# finalpcbv2.net
KiCad netlist of a schematic drawn in EAGLE
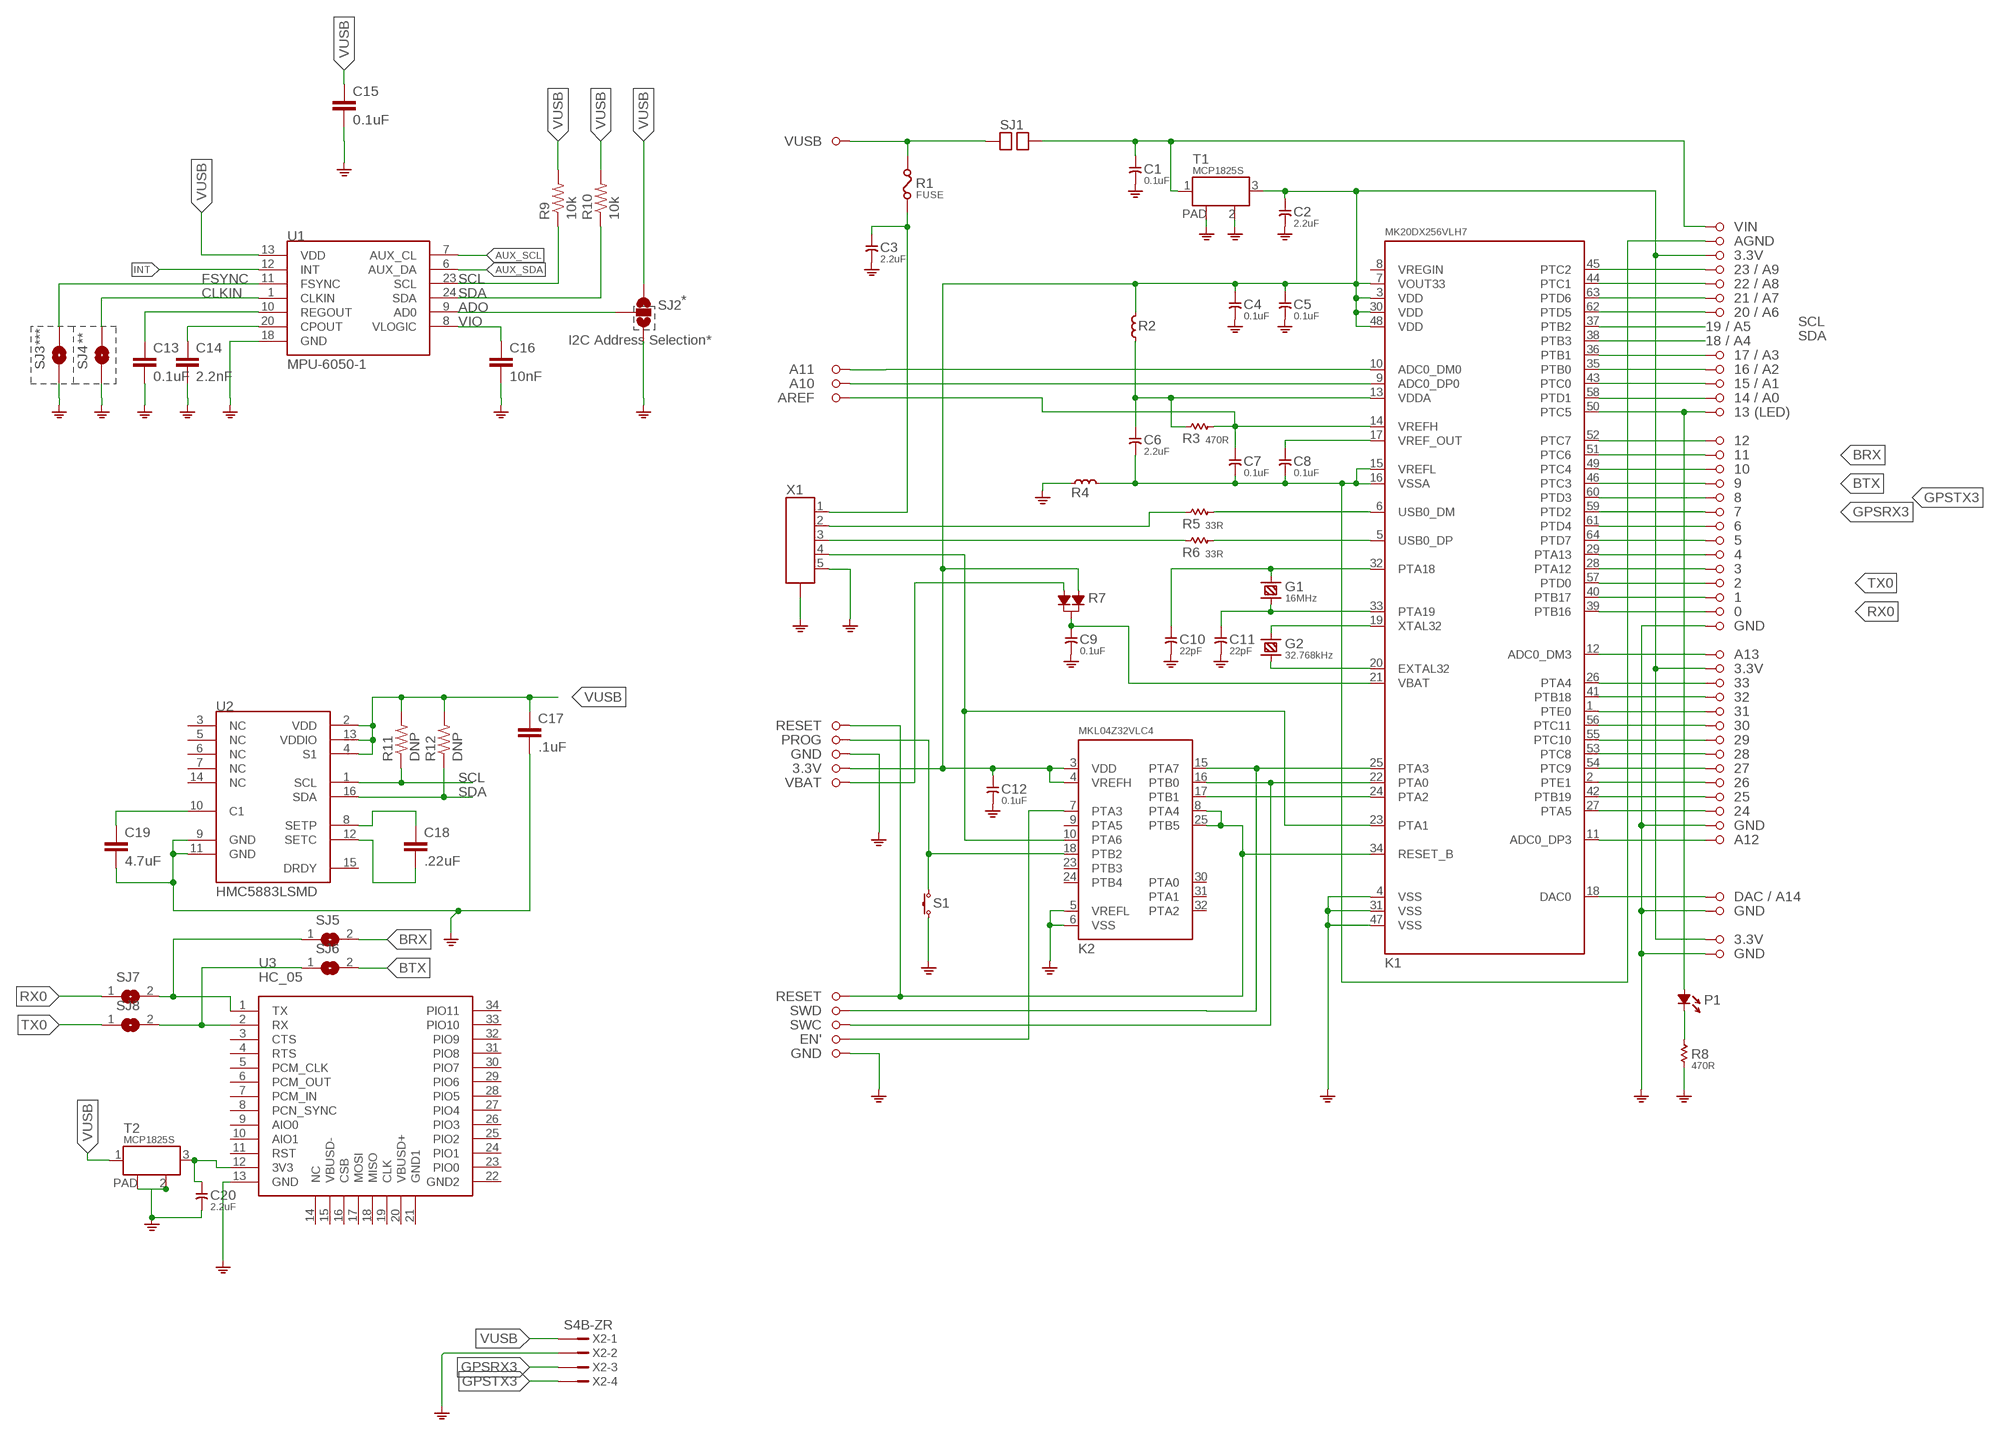
[diagram p0: schematic, sheet 1]

(export (version "E")
  (design (tool "Eeschema 10.0.6"))
  (components
    (comp (ref "C1")
      (value "0.1uF")
      (footprint "eagle-import:C0603")
      (fields (field (name "MF") "Murata Electronics") (field (name "MPN") "GRM188R71C104KA01D"))
      (libsource (lib "eagle-import") (part "CAPACITOR-0.1UF"))
    )
    (comp (ref "C2")
      (value "2.2uF")
      (footprint "eagle-import:C0805")
      (fields (field (name "MF") "Taiyo Yuden") (field (name "MPN") "TMK212B7225KG-TR"))
      (libsource (lib "eagle-import") (part "CAPACITOR-2.2UF"))
    )
    (comp (ref "C3")
      (value "2.2uF")
      (footprint "eagle-import:C0805")
      (fields (field (name "MF") "Taiyo Yuden") (field (name "MPN") "TMK212B7225KG-TR"))
      (libsource (lib "eagle-import") (part "CAPACITOR-2.2UF"))
    )
    (comp (ref "C4")
      (value "0.1uF")
      (footprint "eagle-import:C0603")
      (fields (field (name "MF") "Murata Electronics") (field (name "MPN") "GRM188R71C104KA01D"))
      (libsource (lib "eagle-import") (part "CAPACITOR-0.1UF"))
    )
    (comp (ref "C5")
      (value "0.1uF")
      (footprint "eagle-import:C0603")
      (fields (field (name "MF") "Murata Electronics") (field (name "MPN") "GRM188R71C104KA01D"))
      (libsource (lib "eagle-import") (part "CAPACITOR-0.1UF"))
    )
    (comp (ref "C6")
      (value "2.2uF")
      (footprint "eagle-import:C0805")
      (fields (field (name "MF") "Taiyo Yuden") (field (name "MPN") "TMK212B7225KG-TR"))
      (libsource (lib "eagle-import") (part "CAPACITOR-2.2UF"))
    )
    (comp (ref "C7")
      (value "0.1uF")
      (footprint "eagle-import:C0603")
      (fields (field (name "MF") "Murata Electronics") (field (name "MPN") "GRM188R71C104KA01D"))
      (libsource (lib "eagle-import") (part "CAPACITOR-0.1UF"))
    )
    (comp (ref "C8")
      (value "0.1uF")
      (footprint "eagle-import:C0603")
      (fields (field (name "MF") "Murata Electronics") (field (name "MPN") "GRM188R71C104KA01D"))
      (libsource (lib "eagle-import") (part "CAPACITOR-0.1UF"))
    )
    (comp (ref "C9")
      (value "0.1uF")
      (footprint "eagle-import:C0603")
      (fields (field (name "MF") "Murata Electronics") (field (name "MPN") "GRM188R71C104KA01D"))
      (libsource (lib "eagle-import") (part "CAPACITOR-0.1UF"))
    )
    (comp (ref "C10")
      (value "22pF")
      (footprint "eagle-import:C0603")
      (fields (field (name "MF") "Vishay / Vitramon") (field (name "MPN") "VJ0603A220JXACW1BC"))
      (libsource (lib "eagle-import") (part "CAPACITOR-22PF"))
    )
    (comp (ref "C11")
      (value "22pF")
      (footprint "eagle-import:C0603")
      (fields (field (name "MF") "Vishay / Vitramon") (field (name "MPN") "VJ0603A220JXACW1BC"))
      (libsource (lib "eagle-import") (part "CAPACITOR-22PF"))
    )
    (comp (ref "C12")
      (value "0.1uF")
      (footprint "eagle-import:C0603")
      (fields (field (name "MF") "Murata Electronics") (field (name "MPN") "GRM188R71C104KA01D"))
      (libsource (lib "eagle-import") (part "CAPACITOR-0.1UF"))
    )
    (comp (ref "C13")
      (value "0.1uF")
      (footprint "eagle-import:0603-CAP")
      (libsource (lib "eagle-import") (part "CAP0603-CAP"))
    )
    (comp (ref "C14")
      (value "2.2nF")
      (footprint "eagle-import:0603-CAP")
      (libsource (lib "eagle-import") (part "CAP0603-CAP"))
    )
    (comp (ref "C15")
      (value "0.1uF")
      (footprint "eagle-import:0603-CAP")
      (libsource (lib "eagle-import") (part "CAP0603-CAP"))
    )
    (comp (ref "C16")
      (value "10nF")
      (footprint "eagle-import:0603-CAP")
      (libsource (lib "eagle-import") (part "CAP0603-CAP"))
    )
    (comp (ref "C17")
      (value ".1uF")
      (footprint "eagle-import:0402-CAP")
      (libsource (lib "eagle-import") (part "CAP0402-CAP"))
    )
    (comp (ref "C18")
      (value ".22uF")
      (footprint "eagle-import:0402-CAP")
      (libsource (lib "eagle-import") (part "CAP0402-CAP"))
    )
    (comp (ref "C19")
      (value "4.7uF")
      (footprint "eagle-import:0402-CAP")
      (libsource (lib "eagle-import") (part "CAP0402-CAP"))
    )
    (comp (ref "C20")
      (value "2.2uF")
      (footprint "eagle-import:C0805")
      (fields (field (name "MF") "Taiyo Yuden") (field (name "MPN") "TMK212B7225KG-TR"))
      (libsource (lib "eagle-import") (part "CAPACITOR-2.2UF"))
    )
    (comp (ref "G1")
      (value "16MHz")
      (footprint "eagle-import:HC49US")
      (fields (field (name "MF") "ABRACON") (field (name "MPN") "ABL-16.000MHz-B1U"))
      (libsource (lib "eagle-import") (part "CRYSTAL-HC49US"))
    )
    (comp (ref "G2")
      (value "32.768kHz")
      (footprint "eagle-import:TC26H")
      (fields (field (name "MF") "Citizen FineDevice") (field (name "MPN") " CFS206-32.768KDZF-UB"))
      (libsource (lib "eagle-import") (part "CRYSTAL-TC26H"))
    )
    (comp (ref "K1")
      (value "MK20DX256VLH7")
      (footprint "eagle-import:LQFP64-05")
      (fields (field (name "MF") "NXP"))
      (libsource (lib "eagle-import") (part "MK20DX256VLH7"))
    )
    (comp (ref "K2")
      (value "MKL04Z32VLC4")
      (footprint "eagle-import:LQFP32-08")
      (fields (field (name "MF") "PJRC") (field (name "MPN") "IC_MKL04Z32_TQFP32"))
      (libsource (lib "eagle-import") (part "MKL04Z32VLC4"))
    )
    (comp (ref "P1")
      (value "LED")
      (footprint "eagle-import:LED-0805")
      (fields (field (name "MF") "ROHM Semiconductor") (field (name "MPN") "SML-211DTT86"))
      (libsource (lib "eagle-import") (part "LED"))
    )
    (comp (ref "R1")
      (value "FUSE")
      (footprint "eagle-import:F0805")
      (fields (field (name "MF") "Bel Fuse") (field (name "MPN") "0ZCK0050FF2E"))
      (libsource (lib "eagle-import") (part "FUSE"))
    )
    (comp (ref "R2")
      (value "FERRITE")
      (footprint "eagle-import:L0603")
      (fields (field (name "MF") "Murata Electronics") (field (name "MPN") " BLM18AG601SN1D"))
      (libsource (lib "eagle-import") (part "FERRITE"))
    )
    (comp (ref "R3")
      (value "470R")
      (footprint "eagle-import:R0603")
      (fields (field (name "MF") "Vishay") (field (name "MPN") "CRCW0603470RFKEA"))
      (libsource (lib "eagle-import") (part "RESISTOR-470R"))
    )
    (comp (ref "R4")
      (value "FERRITE")
      (footprint "eagle-import:L0603")
      (fields (field (name "MF") "Murata Electronics") (field (name "MPN") " BLM18AG601SN1D"))
      (libsource (lib "eagle-import") (part "FERRITE"))
    )
    (comp (ref "R5")
      (value "33R")
      (footprint "eagle-import:R0603")
      (fields (field (name "MF") "Panasonic") (field (name "MPN") "ERJ-PA3F33R0V"))
      (libsource (lib "eagle-import") (part "RESISTOR-33R"))
    )
    (comp (ref "R6")
      (value "33R")
      (footprint "eagle-import:R0603")
      (fields (field (name "MF") "Panasonic") (field (name "MPN") "ERJ-PA3F33R0V"))
      (libsource (lib "eagle-import") (part "RESISTOR-33R"))
    )
    (comp (ref "R7")
      (value "DIODE_DUAL")
      (footprint "eagle-import:SOT-23")
      (fields (field (name "MF") "NXP Semiconductors") (field (name "MPN") "BAT54C,215"))
      (libsource (lib "eagle-import") (part "DIODE_DUAL"))
    )
    (comp (ref "R8")
      (value "470R")
      (footprint "eagle-import:R0603")
      (fields (field (name "MF") "Vishay") (field (name "MPN") "CRCW0603470RFKEA"))
      (libsource (lib "eagle-import") (part "RESISTOR-470R"))
    )
    (comp (ref "R9")
      (value "10k")
      (footprint "eagle-import:0603-RES")
      (libsource (lib "eagle-import") (part "RESISTOR0603-RES"))
    )
    (comp (ref "R10")
      (value "10k")
      (footprint "eagle-import:0603-RES")
      (libsource (lib "eagle-import") (part "RESISTOR0603-RES"))
    )
    (comp (ref "R11")
      (value "DNP")
      (footprint "eagle-import:0402-RES")
      (libsource (lib "eagle-import") (part "RESISTOR0402-RES"))
    )
    (comp (ref "R12")
      (value "DNP")
      (footprint "eagle-import:0402-RES")
      (libsource (lib "eagle-import") (part "RESISTOR0402-RES"))
    )
    (comp (ref "S1")
      (value "TACT_SWITCH")
      (footprint "eagle-import:ALPS_SKHH")
      (fields (field (name "MF") "ALPS") (field (name "MPN") "SKHHPKA010"))
      (libsource (lib "eagle-import") (part "TACT_SWITCH"))
    )
    (comp (ref "SJ1")
      (value "SOLDERJUMPER")
      (footprint "eagle-import:SOLDERJUMPER")
      (libsource (lib "eagle-import") (part "SOLDERJUMPER"))
    )
    (comp (ref "SJ2")
      (value "SOLDERJUMPER_2WAYPASTE2&3")
      (footprint "eagle-import:SJ_3_PASTE2&3")
      (libsource (lib "eagle-import") (part "SOLDERJUMPER_2WAYPASTE2&3"))
    )
    (comp (ref "SJ3")
      (value "SOLDERJUMPERTRACE")
      (footprint "eagle-import:SJ_2S-TRACE")
      (libsource (lib "eagle-import") (part "SOLDERJUMPERTRACE"))
    )
    (comp (ref "SJ4")
      (value "SOLDERJUMPERTRACE")
      (footprint "eagle-import:SJ_2S-TRACE")
      (libsource (lib "eagle-import") (part "SOLDERJUMPERTRACE"))
    )
    (comp (ref "SJ5") (value "SJ") (footprint "eagle-import:SJ") (libsource (lib "eagle-import") (part "SJ")))
    (comp (ref "SJ6") (value "SJ") (footprint "eagle-import:SJ") (libsource (lib "eagle-import") (part "SJ")))
    (comp (ref "SJ7") (value "SJ") (footprint "eagle-import:SJ") (libsource (lib "eagle-import") (part "SJ")))
    (comp (ref "SJ8") (value "SJ") (footprint "eagle-import:SJ") (libsource (lib "eagle-import") (part "SJ")))
    (comp (ref "SX1")
      (value "PIN")
      (footprint "eagle-import:PTH_39MIL")
      (libsource (lib "eagle-import") (part "PIN"))
    )
    (comp (ref "SX2")
      (value "PIN")
      (footprint "eagle-import:PTH_39MIL")
      (libsource (lib "eagle-import") (part "PIN"))
    )
    (comp (ref "SX3")
      (value "PIN")
      (footprint "eagle-import:PTH_39MIL")
      (libsource (lib "eagle-import") (part "PIN"))
    )
    (comp (ref "SX4")
      (value "PIN")
      (footprint "eagle-import:PTH_39MIL")
      (libsource (lib "eagle-import") (part "PIN"))
    )
    (comp (ref "SX5")
      (value "PIN")
      (footprint "eagle-import:PTH_39MIL")
      (libsource (lib "eagle-import") (part "PIN"))
    )
    (comp (ref "SX6")
      (value "PIN")
      (footprint "eagle-import:PTH_39MIL")
      (libsource (lib "eagle-import") (part "PIN"))
    )
    (comp (ref "SX7")
      (value "PIN")
      (footprint "eagle-import:PTH_39MIL")
      (libsource (lib "eagle-import") (part "PIN"))
    )
    (comp (ref "SX8")
      (value "PIN")
      (footprint "eagle-import:PTH_39MIL")
      (libsource (lib "eagle-import") (part "PIN"))
    )
    (comp (ref "SX11")
      (value "PIN")
      (footprint "eagle-import:PTH_39MIL")
      (libsource (lib "eagle-import") (part "PIN"))
    )
    (comp (ref "SX12")
      (value "PIN")
      (footprint "eagle-import:PTH_39MIL")
      (libsource (lib "eagle-import") (part "PIN"))
    )
    (comp (ref "SX13")
      (value "PIN")
      (footprint "eagle-import:PTH_39MIL")
      (libsource (lib "eagle-import") (part "PIN"))
    )
    (comp (ref "SX14")
      (value "PIN")
      (footprint "eagle-import:PTH_39MIL")
      (libsource (lib "eagle-import") (part "PIN"))
    )
    (comp (ref "SX15")
      (value "PIN")
      (footprint "eagle-import:PTH_39MIL")
      (libsource (lib "eagle-import") (part "PIN"))
    )
    (comp (ref "SX16")
      (value "PIN")
      (footprint "eagle-import:PTH_39MIL")
      (libsource (lib "eagle-import") (part "PIN"))
    )
    (comp (ref "SX17")
      (value "PIN")
      (footprint "eagle-import:PTH_39MIL")
      (libsource (lib "eagle-import") (part "PIN"))
    )
    (comp (ref "SX18")
      (value "PIN")
      (footprint "eagle-import:PTH_39MIL")
      (libsource (lib "eagle-import") (part "PIN"))
    )
    (comp (ref "SX19")
      (value "PIN")
      (footprint "eagle-import:PTH_39MIL")
      (libsource (lib "eagle-import") (part "PIN"))
    )
    (comp (ref "SX20")
      (value "PIN")
      (footprint "eagle-import:PTH_39MIL")
      (libsource (lib "eagle-import") (part "PIN"))
    )
    (comp (ref "SX21")
      (value "PIN")
      (footprint "eagle-import:PTH_39MIL")
      (libsource (lib "eagle-import") (part "PIN"))
    )
    (comp (ref "SX22")
      (value "PIN")
      (footprint "eagle-import:PTH_39MIL")
      (libsource (lib "eagle-import") (part "PIN"))
    )
    (comp (ref "SX23")
      (value "PIN")
      (footprint "eagle-import:PTH_39MIL")
      (libsource (lib "eagle-import") (part "PIN"))
    )
    (comp (ref "SX24")
      (value "PIN")
      (footprint "eagle-import:PTH_39MIL")
      (libsource (lib "eagle-import") (part "PIN"))
    )
    (comp (ref "SX25")
      (value "PIN")
      (footprint "eagle-import:PTH_39MIL")
      (libsource (lib "eagle-import") (part "PIN"))
    )
    (comp (ref "SX26")
      (value "PIN")
      (footprint "eagle-import:PTH_39MIL")
      (libsource (lib "eagle-import") (part "PIN"))
    )
    (comp (ref "SX27")
      (value "PIN")
      (footprint "eagle-import:PTH_39MIL")
      (libsource (lib "eagle-import") (part "PIN"))
    )
    (comp (ref "SX28")
      (value "PIN")
      (footprint "eagle-import:PTH_39MIL")
      (libsource (lib "eagle-import") (part "PIN"))
    )
    (comp (ref "SX29")
      (value "PIN")
      (footprint "eagle-import:PTH_39MIL")
      (libsource (lib "eagle-import") (part "PIN"))
    )
    (comp (ref "SX30")
      (value "PIN")
      (footprint "eagle-import:PTH_39MIL")
      (libsource (lib "eagle-import") (part "PIN"))
    )
    (comp (ref "SX31")
      (value "PIN")
      (footprint "eagle-import:PTH_39MIL")
      (libsource (lib "eagle-import") (part "PIN"))
    )
    (comp (ref "SX32")
      (value "PIN")
      (footprint "eagle-import:PTH_39MIL")
      (libsource (lib "eagle-import") (part "PIN"))
    )
    (comp (ref "SX33")
      (value "PIN")
      (footprint "eagle-import:PTH_39MIL")
      (libsource (lib "eagle-import") (part "PIN"))
    )
    (comp (ref "SX34")
      (value "PIN")
      (footprint "eagle-import:PTH_39MIL")
      (libsource (lib "eagle-import") (part "PIN"))
    )
    (comp (ref "SX35")
      (value "PIN")
      (footprint "eagle-import:PTH_39MIL")
      (libsource (lib "eagle-import") (part "PIN"))
    )
    (comp (ref "SX36")
      (value "PIN")
      (footprint "eagle-import:PTH_39MIL")
      (libsource (lib "eagle-import") (part "PIN"))
    )
    (comp (ref "SX37")
      (value "PIN")
      (footprint "eagle-import:PTH_39MIL")
      (libsource (lib "eagle-import") (part "PIN"))
    )
    (comp (ref "SX38")
      (value "PIN")
      (footprint "eagle-import:PTH_39MIL")
      (libsource (lib "eagle-import") (part "PIN"))
    )
    (comp (ref "SX39")
      (value "PIN")
      (footprint "eagle-import:PTH_39MIL")
      (libsource (lib "eagle-import") (part "PIN"))
    )
    (comp (ref "SX40")
      (value "PIN")
      (footprint "eagle-import:PTH_39MIL")
      (libsource (lib "eagle-import") (part "PIN"))
    )
    (comp (ref "SX41")
      (value "PIN")
      (footprint "eagle-import:PTH_39MIL")
      (libsource (lib "eagle-import") (part "PIN"))
    )
    (comp (ref "SX42")
      (value "PIN")
      (footprint "eagle-import:PTH_39MIL")
      (libsource (lib "eagle-import") (part "PIN"))
    )
    (comp (ref "SX43")
      (value "PIN")
      (footprint "eagle-import:PTH_39MIL")
      (libsource (lib "eagle-import") (part "PIN"))
    )
    (comp (ref "SX44")
      (value "PIN")
      (footprint "eagle-import:PTH_39MIL")
      (libsource (lib "eagle-import") (part "PIN"))
    )
    (comp (ref "SX45")
      (value "PIN")
      (footprint "eagle-import:PTH_39MIL")
      (libsource (lib "eagle-import") (part "PIN"))
    )
    (comp (ref "SX46")
      (value "PIN")
      (footprint "eagle-import:PTH_39MIL")
      (libsource (lib "eagle-import") (part "PIN"))
    )
    (comp (ref "SX47")
      (value "PIN")
      (footprint "eagle-import:PTH_39MIL")
      (libsource (lib "eagle-import") (part "PIN"))
    )
    (comp (ref "SX48")
      (value "PIN")
      (footprint "eagle-import:PTH_39MIL")
      (libsource (lib "eagle-import") (part "PIN"))
    )
    (comp (ref "SX49")
      (value "PIN")
      (footprint "eagle-import:PTH_39MIL")
      (libsource (lib "eagle-import") (part "PIN"))
    )
    (comp (ref "SX50")
      (value "PIN")
      (footprint "eagle-import:PTH_39MIL")
      (libsource (lib "eagle-import") (part "PIN"))
    )
    (comp (ref "SX51")
      (value "PIN")
      (footprint "eagle-import:PTH_39MIL")
      (libsource (lib "eagle-import") (part "PIN"))
    )
    (comp (ref "SX52")
      (value "PIN")
      (footprint "eagle-import:PTH_39MIL")
      (libsource (lib "eagle-import") (part "PIN"))
    )
    (comp (ref "SX53")
      (value "PIN")
      (footprint "eagle-import:PTH_39MIL")
      (libsource (lib "eagle-import") (part "PIN"))
    )
    (comp (ref "SX54")
      (value "PIN")
      (footprint "eagle-import:PTH_39MIL")
      (libsource (lib "eagle-import") (part "PIN"))
    )
    (comp (ref "SX55")
      (value "PIN")
      (footprint "eagle-import:PTH_39MIL")
      (libsource (lib "eagle-import") (part "PIN"))
    )
    (comp (ref "SX56")
      (value "PIN")
      (footprint "eagle-import:PTH_39MIL")
      (libsource (lib "eagle-import") (part "PIN"))
    )
    (comp (ref "SX57")
      (value "PIN")
      (footprint "eagle-import:PTH_39MIL")
      (libsource (lib "eagle-import") (part "PIN"))
    )
    (comp (ref "SX58")
      (value "PIN")
      (footprint "eagle-import:PTH_39MIL")
      (libsource (lib "eagle-import") (part "PIN"))
    )
    (comp (ref "SX59")
      (value "PIN")
      (footprint "eagle-import:PTH_39MIL")
      (libsource (lib "eagle-import") (part "PIN"))
    )
    (comp (ref "SX60")
      (value "PIN")
      (footprint "eagle-import:PTH_39MIL")
      (libsource (lib "eagle-import") (part "PIN"))
    )
    (comp (ref "T1")
      (value "MCP1825S")
      (footprint "eagle-import:SOT-223")
      (fields (field (name "MF") "Microchip Technology") (field (name "MPN") "MCP1825S-3302E/DB"))
      (libsource (lib "eagle-import") (part "LDO"))
    )
    (comp (ref "T2")
      (value "MCP1825S")
      (footprint "eagle-import:SOT-223")
      (fields (field (name "MF") "Microchip Technology") (field (name "MPN") "MCP1825S-3302E/DB"))
      (libsource (lib "eagle-import") (part "LDO"))
    )
    (comp (ref "U1")
      (value "MPU-6050-1")
      (footprint "eagle-import:QFN-24-4MM2")
      (libsource (lib "eagle-import") (part "MPU-6050-1"))
    )
    (comp (ref "U2")
      (value "HMC5883LSMD")
      (footprint "eagle-import:16LPCC")
      (libsource (lib "eagle-import") (part "HMC5883LSMD"))
    )
    (comp (ref "U3")
      (value "HC_05")
      (footprint "eagle-import:BLUETOOTH_SMD")
      (libsource (lib "eagle-import") (part "HC_05"))
    )
    (comp (ref "X1")
      (value "MINI-USB")
      (footprint "eagle-import:MOLEX_SD-67503-010")
      (fields (field (name "MF") "MOLEX") (field (name "MPN") "0675031020"))
      (libsource (lib "eagle-import") (part "MINI-USBMOLEX_0675031230"))
    )
    (comp (ref "X2")
      (value "S4B-ZR")
      (footprint "eagle-import:S4B-ZR")
      (fields (field (name "MF") "FARNELL") (field (name "MPN") "S4B-ZR(LF)(SN)"))
      (libsource (lib "eagle-import") (part "?4B-ZRS"))
    )
  )
  (nets
    (net (code "1") (name "/ADO") (class "Default")
      (node (ref "SJ2") (pin "2") (pinfunction "2_2") (pintype "passive"))
      (node (ref "U1") (pin "9") (pinfunction "AD0_9") (pintype "bidirectional"))
    )
    (net (code "2") (name "/CLKIN") (class "Default")
      (node (ref "SJ4") (pin "2") (pinfunction "2_2") (pintype "passive"))
      (node (ref "U1") (pin "1") (pinfunction "CLKIN_1") (pintype "bidirectional"))
    )
    (net (code "3") (name "/FSYNC") (class "Default")
      (node (ref "SJ3") (pin "2") (pinfunction "2_2") (pintype "passive"))
      (node (ref "U1") (pin "11") (pinfunction "FSYNC_11") (pintype "bidirectional"))
    )
    (net (code "4") (name "/SCL") (class "Default")
      (node (ref "K1") (pin "37") (pinfunction "PTB2_37") (pintype "bidirectional"))
      (node (ref "R11") (pin "1") (pinfunction "1_1") (pintype "passive"))
      (node (ref "R9") (pin "1") (pinfunction "1_1") (pintype "passive"))
      (node (ref "U1") (pin "23") (pinfunction "SCL_23") (pintype "bidirectional"))
      (node (ref "U2") (pin "1") (pinfunction "SCL_1") (pintype "bidirectional"))
    )
    (net (code "5") (name "/SDA") (class "Default")
      (node (ref "K1") (pin "38") (pinfunction "PTB3_38") (pintype "bidirectional"))
      (node (ref "R10") (pin "1") (pinfunction "1_1") (pintype "passive"))
      (node (ref "R12") (pin "1") (pinfunction "1_1") (pintype "passive"))
      (node (ref "U1") (pin "24") (pinfunction "SDA_24") (pintype "bidirectional"))
      (node (ref "U2") (pin "16") (pinfunction "SDA_16") (pintype "bidirectional"))
    )
    (net (code "6") (name "/VIO") (class "Default")
      (node (ref "C16") (pin "1") (pinfunction "1_1") (pintype "passive"))
      (node (ref "U1") (pin "8") (pinfunction "VLOGIC_8") (pintype "bidirectional"))
    )
    (net (code "7") (name "AUX_SCL") (class "Default")
      (node (ref "U1") (pin "7") (pinfunction "AUX_CL_7") (pintype "bidirectional"))
    )
    (net (code "8") (name "AUX_SDA") (class "Default")
      (node (ref "U1") (pin "6") (pinfunction "AUX_DA_6") (pintype "bidirectional"))
    )
    (net (code "9") (name "BRX") (class "Default")
      (node (ref "K1") (pin "49") (pinfunction "PTC4_49") (pintype "bidirectional"))
      (node (ref "SJ5") (pin "2") (pinfunction "2_2") (pintype "passive"))
      (node (ref "SX21") (pin "1") (pinfunction "P$1_1") (pintype "bidirectional"))
    )
    (net (code "10") (name "BTX") (class "Default")
      (node (ref "K1") (pin "46") (pinfunction "PTC3_46") (pintype "bidirectional"))
      (node (ref "SJ6") (pin "2") (pinfunction "2_2") (pintype "passive"))
      (node (ref "SX22") (pin "1") (pinfunction "P$1_1") (pintype "bidirectional"))
    )
    (net (code "11") (name "GND") (class "Default")
      (node (ref "C1") (pin "2") (pinfunction "2_2") (pintype "passive"))
      (node (ref "C10") (pin "2") (pinfunction "2_2") (pintype "passive"))
      (node (ref "C11") (pin "2") (pinfunction "2_2") (pintype "passive"))
      (node (ref "C12") (pin "2") (pinfunction "2_2") (pintype "passive"))
      (node (ref "C13") (pin "2") (pinfunction "2_2") (pintype "passive"))
      (node (ref "C14") (pin "2") (pinfunction "2_2") (pintype "passive"))
      (node (ref "C15") (pin "2") (pinfunction "2_2") (pintype "passive"))
      (node (ref "C16") (pin "2") (pinfunction "2_2") (pintype "passive"))
      (node (ref "C17") (pin "2") (pinfunction "2_2") (pintype "passive"))
      (node (ref "C19") (pin "2") (pinfunction "2_2") (pintype "passive"))
      (node (ref "C2") (pin "2") (pinfunction "2_2") (pintype "passive"))
      (node (ref "C20") (pin "2") (pinfunction "2_2") (pintype "passive"))
      (node (ref "C3") (pin "2") (pinfunction "2_2") (pintype "passive"))
      (node (ref "C4") (pin "2") (pinfunction "2_2") (pintype "passive"))
      (node (ref "C5") (pin "2") (pinfunction "2_2") (pintype "passive"))
      (node (ref "C9") (pin "2") (pinfunction "2_2") (pintype "passive"))
      (node (ref "K1") (pin "31") (pinfunction "VSS_31") (pintype "bidirectional"))
      (node (ref "K1") (pin "4") (pinfunction "VSS_4") (pintype "bidirectional"))
      (node (ref "K1") (pin "47") (pinfunction "VSS_47") (pintype "bidirectional"))
      (node (ref "K2") (pin "5") (pinfunction "VREFL_5") (pintype "bidirectional"))
      (node (ref "K2") (pin "6") (pinfunction "VSS_6") (pintype "bidirectional"))
      (node (ref "R4") (pin "1") (pinfunction "1_1") (pintype "passive"))
      (node (ref "R8") (pin "1") (pinfunction "1_1") (pintype "passive"))
      (node (ref "S1") (pin "3") (pinfunction "3_3") (pintype "passive"))
      (node (ref "S1") (pin "4") (pinfunction "3_4") (pintype "passive"))
      (node (ref "SJ2") (pin "3") (pinfunction "3_3") (pintype "passive"))
      (node (ref "SJ3") (pin "1") (pinfunction "1_1") (pintype "passive"))
      (node (ref "SJ4") (pin "1") (pinfunction "1_1") (pintype "passive"))
      (node (ref "SX32") (pin "1") (pinfunction "P$1_1") (pintype "bidirectional"))
      (node (ref "SX42") (pin "1") (pinfunction "P$1_1") (pintype "bidirectional"))
      (node (ref "SX50") (pin "1") (pinfunction "P$1_1") (pintype "bidirectional"))
      (node (ref "SX53") (pin "1") (pinfunction "P$1_1") (pintype "bidirectional"))
      (node (ref "SX55") (pin "1") (pinfunction "P$1_1") (pintype "bidirectional"))
      (node (ref "SX60") (pin "1") (pinfunction "P$1_1") (pintype "bidirectional"))
      (node (ref "T1") (pin "2") (pinfunction "GND_2") (pintype "bidirectional"))
      (node (ref "T1") (pin "PAD") (pinfunction "PAD_PAD") (pintype "bidirectional"))
      (node (ref "T2") (pin "2") (pinfunction "GND_2") (pintype "bidirectional"))
      (node (ref "T2") (pin "PAD") (pinfunction "PAD_PAD") (pintype "bidirectional"))
      (node (ref "U1") (pin "18") (pinfunction "GND_18") (pintype "bidirectional"))
      (node (ref "U2") (pin "11") (pinfunction "GND_11") (pintype "bidirectional"))
      (node (ref "U2") (pin "9") (pinfunction "GND_9") (pintype "bidirectional"))
      (node (ref "U3") (pin "13") (pinfunction "GND_13") (pintype "bidirectional"))
      (node (ref "X1") (pin "5") (pinfunction "5_5") (pintype "input"))
      (node (ref "X1") (pin "P$1") (pinfunction "CASE_P$1") (pintype "input"))
      (node (ref "X1") (pin "P$2") (pinfunction "CASE_P$2") (pintype "input"))
      (node (ref "X1") (pin "P$3") (pinfunction "CASE_P$3") (pintype "input"))
      (node (ref "X1") (pin "P$4") (pinfunction "CASE_P$4") (pintype "input"))
      (node (ref "X1") (pin "P$5") (pinfunction "CASE_P$5") (pintype "input"))
      (node (ref "X1") (pin "P$6") (pinfunction "CASE_P$6") (pintype "input"))
      (node (ref "X2") (pin "2") (pinfunction "1_2") (pintype "passive"))
    )
    (net (code "12") (name "GPSRX3") (class "Default")
      (node (ref "K1") (pin "59") (pinfunction "PTD2_59") (pintype "bidirectional"))
      (node (ref "SX24") (pin "1") (pinfunction "P$1_1") (pintype "bidirectional"))
      (node (ref "X2") (pin "3") (pinfunction "1_3") (pintype "passive"))
    )
    (net (code "13") (name "GPSTX3") (class "Default")
      (node (ref "K1") (pin "60") (pinfunction "PTD3_60") (pintype "bidirectional"))
      (node (ref "SX23") (pin "1") (pinfunction "P$1_1") (pintype "bidirectional"))
      (node (ref "X2") (pin "4") (pinfunction "1_4") (pintype "passive"))
    )
    (net (code "14") (name "INT") (class "Default")
      (node (ref "U1") (pin "12") (pinfunction "INT_12") (pintype "bidirectional"))
    )
    (net (code "15") (name "Net-(C3-Pad1)") (class "Default")
      (node (ref "C3") (pin "1") (pinfunction "1_1") (pintype "passive"))
      (node (ref "R1") (pin "1") (pinfunction "1_1") (pintype "bidirectional"))
      (node (ref "X1") (pin "1") (pinfunction "1_1") (pintype "input"))
    )
    (net (code "16") (name "Net-(G2-1)") (class "Default")
      (node (ref "G2") (pin "2") (pinfunction "1_2") (pintype "passive"))
      (node (ref "K1") (pin "19") (pinfunction "XTAL32_19") (pintype "bidirectional"))
    )
    (net (code "17") (name "Net-(G2-2)") (class "Default")
      (node (ref "G2") (pin "1") (pinfunction "2_1") (pintype "passive"))
      (node (ref "K1") (pin "20") (pinfunction "EXTAL32_20") (pintype "bidirectional"))
    )
    (net (code "18") (name "Net-(K1-ADC0_DM0)") (class "Default")
      (node (ref "K1") (pin "10") (pinfunction "ADC0_DM0_10") (pintype "bidirectional"))
      (node (ref "SX12") (pin "1") (pinfunction "P$1_1") (pintype "bidirectional"))
    )
    (net (code "19") (name "Net-(K1-ADC0_DM3)") (class "Default")
      (node (ref "K1") (pin "12") (pinfunction "ADC0_DM3_12") (pintype "bidirectional"))
      (node (ref "SX33") (pin "1") (pinfunction "P$1_1") (pintype "bidirectional"))
    )
    (net (code "20") (name "Net-(K1-ADC0_DP0)") (class "Default")
      (node (ref "K1") (pin "9") (pinfunction "ADC0_DP0_9") (pintype "bidirectional"))
      (node (ref "SX14") (pin "1") (pinfunction "P$1_1") (pintype "bidirectional"))
    )
    (net (code "21") (name "Net-(K1-ADC0_DP3)") (class "Default")
      (node (ref "K1") (pin "11") (pinfunction "ADC0_DP3_11") (pintype "bidirectional"))
      (node (ref "SX51") (pin "1") (pinfunction "P$1_1") (pintype "bidirectional"))
    )
    (net (code "22") (name "Net-(K1-DAC0)") (class "Default")
      (node (ref "K1") (pin "18") (pinfunction "DAC0_18") (pintype "bidirectional"))
      (node (ref "SX52") (pin "1") (pinfunction "P$1_1") (pintype "bidirectional"))
    )
    (net (code "23") (name "Net-(K1-PTA0)") (class "Default")
      (node (ref "K1") (pin "22") (pinfunction "PTA0_22") (pintype "bidirectional"))
      (node (ref "K2") (pin "16") (pinfunction "PTB0_16") (pintype "bidirectional"))
      (node (ref "SX58") (pin "1") (pinfunction "P$1_1") (pintype "bidirectional"))
    )
    (net (code "24") (name "Net-(K1-PTA1)") (class "Default")
      (node (ref "K1") (pin "23") (pinfunction "PTA1_23") (pintype "bidirectional"))
      (node (ref "K2") (pin "10") (pinfunction "PTA6_10") (pintype "bidirectional"))
      (node (ref "X1") (pin "4") (pinfunction "4_4") (pintype "input"))
    )
    (net (code "25") (name "Net-(K1-PTA2)") (class "Default")
      (node (ref "K1") (pin "24") (pinfunction "PTA2_24") (pintype "bidirectional"))
      (node (ref "K2") (pin "17") (pinfunction "PTB1_17") (pintype "bidirectional"))
    )
    (net (code "26") (name "Net-(K1-PTA3)") (class "Default")
      (node (ref "K1") (pin "25") (pinfunction "PTA3_25") (pintype "bidirectional"))
      (node (ref "K2") (pin "15") (pinfunction "PTA7_15") (pintype "bidirectional"))
      (node (ref "SX57") (pin "1") (pinfunction "P$1_1") (pintype "bidirectional"))
    )
    (net (code "27") (name "Net-(K1-PTA4)") (class "Default")
      (node (ref "K1") (pin "26") (pinfunction "PTA4_26") (pintype "bidirectional"))
      (node (ref "SX35") (pin "1") (pinfunction "P$1_1") (pintype "bidirectional"))
    )
    (net (code "28") (name "Net-(K1-PTA5)") (class "Default")
      (node (ref "K1") (pin "27") (pinfunction "PTA5_27") (pintype "bidirectional"))
      (node (ref "SX49") (pin "1") (pinfunction "P$1_1") (pintype "bidirectional"))
    )
    (net (code "29") (name "Net-(K1-PTA12)") (class "Default")
      (node (ref "K1") (pin "28") (pinfunction "PTA12_28") (pintype "bidirectional"))
      (node (ref "SX28") (pin "1") (pinfunction "P$1_1") (pintype "bidirectional"))
    )
    (net (code "30") (name "Net-(K1-PTA13)") (class "Default")
      (node (ref "K1") (pin "29") (pinfunction "PTA13_29") (pintype "bidirectional"))
      (node (ref "SX27") (pin "1") (pinfunction "P$1_1") (pintype "bidirectional"))
    )
    (net (code "31") (name "Net-(K1-PTA18)") (class "Default")
      (node (ref "C10") (pin "1") (pinfunction "1_1") (pintype "passive"))
      (node (ref "G1") (pin "1") (pinfunction "1_1") (pintype "passive"))
      (node (ref "K1") (pin "32") (pinfunction "PTA18_32") (pintype "bidirectional"))
    )
    (net (code "32") (name "Net-(K1-PTA19)") (class "Default")
      (node (ref "C11") (pin "1") (pinfunction "1_1") (pintype "passive"))
      (node (ref "G1") (pin "2") (pinfunction "2_2") (pintype "passive"))
      (node (ref "K1") (pin "33") (pinfunction "PTA19_33") (pintype "bidirectional"))
    )
    (net (code "33") (name "Net-(K1-PTB0)") (class "Default")
      (node (ref "K1") (pin "35") (pinfunction "PTB0_35") (pintype "bidirectional"))
      (node (ref "SX13") (pin "1") (pinfunction "P$1_1") (pintype "bidirectional"))
    )
    (net (code "34") (name "Net-(K1-PTB1)") (class "Default")
      (node (ref "K1") (pin "36") (pinfunction "PTB1_36") (pintype "bidirectional"))
      (node (ref "SX11") (pin "1") (pinfunction "P$1_1") (pintype "bidirectional"))
    )
    (net (code "35") (name "Net-(K1-PTB18)") (class "Default")
      (node (ref "K1") (pin "41") (pinfunction "PTB18_41") (pintype "bidirectional"))
      (node (ref "SX36") (pin "1") (pinfunction "P$1_1") (pintype "bidirectional"))
    )
    (net (code "36") (name "Net-(K1-PTB19)") (class "Default")
      (node (ref "K1") (pin "42") (pinfunction "PTB19_42") (pintype "bidirectional"))
      (node (ref "SX48") (pin "1") (pinfunction "P$1_1") (pintype "bidirectional"))
    )
    (net (code "37") (name "Net-(K1-PTC0)") (class "Default")
      (node (ref "K1") (pin "43") (pinfunction "PTC0_43") (pintype "bidirectional"))
      (node (ref "SX15") (pin "1") (pinfunction "P$1_1") (pintype "bidirectional"))
    )
    (net (code "38") (name "Net-(K1-PTC1)") (class "Default")
      (node (ref "K1") (pin "44") (pinfunction "PTC1_44") (pintype "bidirectional"))
      (node (ref "SX6") (pin "1") (pinfunction "P$1_1") (pintype "bidirectional"))
    )
    (net (code "39") (name "Net-(K1-PTC2)") (class "Default")
      (node (ref "K1") (pin "45") (pinfunction "PTC2_45") (pintype "bidirectional"))
      (node (ref "SX5") (pin "1") (pinfunction "P$1_1") (pintype "bidirectional"))
    )
    (net (code "40") (name "Net-(K1-PTC5)") (class "Default")
      (node (ref "K1") (pin "50") (pinfunction "PTC5_50") (pintype "bidirectional"))
      (node (ref "P1") (pin "+") (pinfunction "+_+") (pintype "passive"))
      (node (ref "SX18") (pin "1") (pinfunction "P$1_1") (pintype "bidirectional"))
    )
    (net (code "41") (name "Net-(K1-PTC6)") (class "Default")
      (node (ref "K1") (pin "51") (pinfunction "PTC6_51") (pintype "bidirectional"))
      (node (ref "SX20") (pin "1") (pinfunction "P$1_1") (pintype "bidirectional"))
    )
    (net (code "42") (name "Net-(K1-PTC7)") (class "Default")
      (node (ref "K1") (pin "52") (pinfunction "PTC7_52") (pintype "bidirectional"))
      (node (ref "SX19") (pin "1") (pinfunction "P$1_1") (pintype "bidirectional"))
    )
    (net (code "43") (name "Net-(K1-PTC8)") (class "Default")
      (node (ref "K1") (pin "53") (pinfunction "PTC8_53") (pintype "bidirectional"))
      (node (ref "SX43") (pin "1") (pinfunction "P$1_1") (pintype "bidirectional"))
    )
    (net (code "44") (name "Net-(K1-PTC9)") (class "Default")
      (node (ref "K1") (pin "54") (pinfunction "PTC9_54") (pintype "bidirectional"))
      (node (ref "SX45") (pin "1") (pinfunction "P$1_1") (pintype "bidirectional"))
    )
    (net (code "45") (name "Net-(K1-PTC10)") (class "Default")
      (node (ref "K1") (pin "55") (pinfunction "PTC10_55") (pintype "bidirectional"))
      (node (ref "SX41") (pin "1") (pinfunction "P$1_1") (pintype "bidirectional"))
    )
    (net (code "46") (name "Net-(K1-PTC11)") (class "Default")
      (node (ref "K1") (pin "56") (pinfunction "PTC11_56") (pintype "bidirectional"))
      (node (ref "SX39") (pin "1") (pinfunction "P$1_1") (pintype "bidirectional"))
    )
    (net (code "47") (name "Net-(K1-PTD0)") (class "Default")
      (node (ref "K1") (pin "57") (pinfunction "PTD0_57") (pintype "bidirectional"))
      (node (ref "SX29") (pin "1") (pinfunction "P$1_1") (pintype "bidirectional"))
    )
    (net (code "48") (name "Net-(K1-PTD1)") (class "Default")
      (node (ref "K1") (pin "58") (pinfunction "PTD1_58") (pintype "bidirectional"))
      (node (ref "SX17") (pin "1") (pinfunction "P$1_1") (pintype "bidirectional"))
    )
    (net (code "49") (name "Net-(K1-PTD4)") (class "Default")
      (node (ref "K1") (pin "61") (pinfunction "PTD4_61") (pintype "bidirectional"))
      (node (ref "SX25") (pin "1") (pinfunction "P$1_1") (pintype "bidirectional"))
    )
    (net (code "50") (name "Net-(K1-PTD5)") (class "Default")
      (node (ref "K1") (pin "62") (pinfunction "PTD5_62") (pintype "bidirectional"))
      (node (ref "SX8") (pin "1") (pinfunction "P$1_1") (pintype "bidirectional"))
    )
    (net (code "51") (name "Net-(K1-PTD6)") (class "Default")
      (node (ref "K1") (pin "63") (pinfunction "PTD6_63") (pintype "bidirectional"))
      (node (ref "SX7") (pin "1") (pinfunction "P$1_1") (pintype "bidirectional"))
    )
    (net (code "52") (name "Net-(K1-PTD7)") (class "Default")
      (node (ref "K1") (pin "64") (pinfunction "PTD7_64") (pintype "bidirectional"))
      (node (ref "SX26") (pin "1") (pinfunction "P$1_1") (pintype "bidirectional"))
    )
    (net (code "53") (name "Net-(K1-PTE0)") (class "Default")
      (node (ref "K1") (pin "1") (pinfunction "PTE0_1") (pintype "bidirectional"))
      (node (ref "SX37") (pin "1") (pinfunction "P$1_1") (pintype "bidirectional"))
    )
    (net (code "54") (name "Net-(K1-PTE1)") (class "Default")
      (node (ref "K1") (pin "2") (pinfunction "PTE1_2") (pintype "bidirectional"))
      (node (ref "SX47") (pin "1") (pinfunction "P$1_1") (pintype "bidirectional"))
    )
    (net (code "55") (name "Net-(K1-RESET_B)") (class "Default")
      (node (ref "K1") (pin "34") (pinfunction "RESET_B_34") (pintype "bidirectional"))
      (node (ref "K2") (pin "25") (pinfunction "PTB5_25") (pintype "bidirectional"))
      (node (ref "K2") (pin "8") (pinfunction "PTA4_8") (pintype "bidirectional"))
      (node (ref "SX38") (pin "1") (pinfunction "P$1_1") (pintype "bidirectional"))
      (node (ref "SX56") (pin "1") (pinfunction "P$1_1") (pintype "bidirectional"))
    )
    (net (code "56") (name "Net-(K1-USB0_DM)") (class "Default")
      (node (ref "K1") (pin "6") (pinfunction "USB0_DM_6") (pintype "bidirectional"))
      (node (ref "R5") (pin "2") (pinfunction "2_2") (pintype "passive"))
    )
    (net (code "57") (name "Net-(K1-USB0_DP)") (class "Default")
      (node (ref "K1") (pin "5") (pinfunction "USB0_DP_5") (pintype "bidirectional"))
      (node (ref "R6") (pin "2") (pinfunction "2_2") (pintype "passive"))
    )
    (net (code "58") (name "Net-(K1-VBAT)") (class "Default")
      (node (ref "C9") (pin "1") (pinfunction "1_1") (pintype "passive"))
      (node (ref "K1") (pin "21") (pinfunction "VBAT_21") (pintype "bidirectional"))
      (node (ref "R7") (pin "3") (pinfunction "3_3") (pintype "bidirectional"))
    )
    (net (code "59") (name "Net-(K1-VDDA)") (class "Default")
      (node (ref "C6") (pin "1") (pinfunction "1_1") (pintype "passive"))
      (node (ref "K1") (pin "13") (pinfunction "VDDA_13") (pintype "bidirectional"))
      (node (ref "R2") (pin "1") (pinfunction "1_1") (pintype "passive"))
      (node (ref "R3") (pin "1") (pinfunction "1_1") (pintype "passive"))
    )
    (net (code "60") (name "Net-(K1-VOUT33)") (class "Default")
      (node (ref "C12") (pin "1") (pinfunction "1_1") (pintype "passive"))
      (node (ref "C2") (pin "1") (pinfunction "1_1") (pintype "passive"))
      (node (ref "C4") (pin "1") (pinfunction "1_1") (pintype "passive"))
      (node (ref "C5") (pin "1") (pinfunction "1_1") (pintype "passive"))
      (node (ref "K1") (pin "3") (pinfunction "VDD_3") (pintype "bidirectional"))
      (node (ref "K1") (pin "30") (pinfunction "VDD_30") (pintype "bidirectional"))
      (node (ref "K1") (pin "48") (pinfunction "VDD_48") (pintype "bidirectional"))
      (node (ref "K1") (pin "7") (pinfunction "VOUT33_7") (pintype "bidirectional"))
      (node (ref "K2") (pin "3") (pinfunction "VDD_3") (pintype "bidirectional"))
      (node (ref "K2") (pin "4") (pinfunction "VREFH_4") (pintype "bidirectional"))
      (node (ref "R2") (pin "2") (pinfunction "2_2") (pintype "passive"))
      (node (ref "R7") (pin "1") (pinfunction "1_1") (pintype "bidirectional"))
      (node (ref "SX34") (pin "1") (pinfunction "P$1_1") (pintype "bidirectional"))
      (node (ref "SX4") (pin "1") (pinfunction "P$1_1") (pintype "bidirectional"))
      (node (ref "SX44") (pin "1") (pinfunction "P$1_1") (pintype "bidirectional"))
      (node (ref "SX54") (pin "1") (pinfunction "P$1_1") (pintype "bidirectional"))
      (node (ref "T1") (pin "3") (pinfunction "OUT_3") (pintype "bidirectional"))
    )
    (net (code "61") (name "Net-(K1-VREFH)") (class "Default")
      (node (ref "C7") (pin "1") (pinfunction "1_1") (pintype "passive"))
      (node (ref "K1") (pin "14") (pinfunction "VREFH_14") (pintype "bidirectional"))
      (node (ref "R3") (pin "2") (pinfunction "2_2") (pintype "passive"))
      (node (ref "SX16") (pin "1") (pinfunction "P$1_1") (pintype "bidirectional"))
    )
    (net (code "62") (name "Net-(K1-VREFL)") (class "Default")
      (node (ref "C6") (pin "2") (pinfunction "2_2") (pintype "passive"))
      (node (ref "C7") (pin "2") (pinfunction "2_2") (pintype "passive"))
      (node (ref "C8") (pin "2") (pinfunction "2_2") (pintype "passive"))
      (node (ref "K1") (pin "15") (pinfunction "VREFL_15") (pintype "bidirectional"))
      (node (ref "K1") (pin "16") (pinfunction "VSSA_16") (pintype "bidirectional"))
      (node (ref "R4") (pin "2") (pinfunction "2_2") (pintype "passive"))
      (node (ref "SX3") (pin "1") (pinfunction "P$1_1") (pintype "bidirectional"))
    )
    (net (code "63") (name "Net-(K1-VREF_OUT)") (class "Default")
      (node (ref "C8") (pin "1") (pinfunction "1_1") (pintype "passive"))
      (node (ref "K1") (pin "17") (pinfunction "VREF_OUT_17") (pintype "bidirectional"))
    )
    (net (code "64") (name "Net-(K2-PTA3)") (class "Default")
      (node (ref "K2") (pin "7") (pinfunction "PTA3_7") (pintype "bidirectional"))
      (node (ref "SX59") (pin "1") (pinfunction "P$1_1") (pintype "bidirectional"))
    )
    (net (code "65") (name "Net-(K2-PTB2)") (class "Default")
      (node (ref "K2") (pin "18") (pinfunction "PTB2_18") (pintype "bidirectional"))
      (node (ref "S1") (pin "1") (pinfunction "1_1") (pintype "passive"))
      (node (ref "S1") (pin "2") (pinfunction "1_2") (pintype "passive"))
      (node (ref "SX40") (pin "1") (pinfunction "P$1_1") (pintype "bidirectional"))
    )
    (net (code "66") (name "Net-(P1-Pad-)") (class "Default")
      (node (ref "P1") (pin "-") (pinfunction "-_-") (pintype "passive"))
      (node (ref "R8") (pin "2") (pinfunction "2_2") (pintype "passive"))
    )
    (net (code "67") (name "Net-(R5-Pad1)") (class "Default")
      (node (ref "R5") (pin "1") (pinfunction "1_1") (pintype "passive"))
      (node (ref "X1") (pin "2") (pinfunction "2_2") (pintype "input"))
    )
    (net (code "68") (name "Net-(R6-Pad1)") (class "Default")
      (node (ref "R6") (pin "1") (pinfunction "1_1") (pintype "passive"))
      (node (ref "X1") (pin "3") (pinfunction "3_3") (pintype "input"))
    )
    (net (code "69") (name "Net-(SX1-P$1)") (class "Default")
      (node (ref "R1") (pin "2") (pinfunction "2_2") (pintype "bidirectional"))
      (node (ref "SJ1") (pin "1") (pinfunction "1_1") (pintype "passive"))
      (node (ref "SX1") (pin "1") (pinfunction "P$1_1") (pintype "bidirectional"))
    )
    (net (code "70") (name "Net-(SX2-P$1)") (class "Default")
      (node (ref "C1") (pin "1") (pinfunction "1_1") (pintype "passive"))
      (node (ref "SJ1") (pin "2") (pinfunction "2_2") (pintype "passive"))
      (node (ref "SX2") (pin "1") (pinfunction "P$1_1") (pintype "bidirectional"))
      (node (ref "T1") (pin "1") (pinfunction "IN_1") (pintype "bidirectional"))
    )
    (net (code "71") (name "Net-(SX46-P$1)") (class "Default")
      (node (ref "R7") (pin "2") (pinfunction "2_2") (pintype "bidirectional"))
      (node (ref "SX46") (pin "1") (pinfunction "P$1_1") (pintype "bidirectional"))
    )
    (net (code "72") (name "Net-(T2-OUT)") (class "Default")
      (node (ref "C20") (pin "1") (pinfunction "1_1") (pintype "passive"))
      (node (ref "T2") (pin "3") (pinfunction "OUT_3") (pintype "bidirectional"))
      (node (ref "U3") (pin "12") (pinfunction "3V3_12") (pintype "bidirectional"))
    )
    (net (code "73") (name "Net-(U1-CPOUT)") (class "Default")
      (node (ref "C14") (pin "1") (pinfunction "1_1") (pintype "passive"))
      (node (ref "U1") (pin "20") (pinfunction "CPOUT_20") (pintype "bidirectional"))
    )
    (net (code "74") (name "Net-(U1-REGOUT)") (class "Default")
      (node (ref "C13") (pin "1") (pinfunction "1_1") (pintype "passive"))
      (node (ref "U1") (pin "10") (pinfunction "REGOUT_10") (pintype "bidirectional"))
    )
    (net (code "75") (name "Net-(U2-C1)") (class "Default")
      (node (ref "C19") (pin "1") (pinfunction "1_1") (pintype "passive"))
      (node (ref "U2") (pin "10") (pinfunction "C1_10") (pintype "bidirectional"))
    )
    (net (code "76") (name "Net-(U2-SETC)") (class "Default")
      (node (ref "C18") (pin "2") (pinfunction "2_2") (pintype "passive"))
      (node (ref "U2") (pin "12") (pinfunction "SETC_12") (pintype "bidirectional"))
    )
    (net (code "77") (name "Net-(U2-SETP)") (class "Default")
      (node (ref "C18") (pin "1") (pinfunction "1_1") (pintype "passive"))
      (node (ref "U2") (pin "8") (pinfunction "SETP_8") (pintype "bidirectional"))
    )
    (net (code "78") (name "Net-(U3-RX)") (class "Default")
      (node (ref "SJ6") (pin "1") (pinfunction "1_1") (pintype "passive"))
      (node (ref "SJ8") (pin "2") (pinfunction "2_2") (pintype "passive"))
      (node (ref "U3") (pin "2") (pinfunction "RX_2") (pintype "bidirectional"))
    )
    (net (code "79") (name "Net-(U3-TX)") (class "Default")
      (node (ref "SJ5") (pin "1") (pinfunction "1_1") (pintype "passive"))
      (node (ref "SJ7") (pin "2") (pinfunction "2_2") (pintype "passive"))
      (node (ref "U3") (pin "1") (pinfunction "TX_1") (pintype "bidirectional"))
    )
    (net (code "80") (name "RX0") (class "Default")
      (node (ref "K1") (pin "39") (pinfunction "PTB16_39") (pintype "bidirectional"))
      (node (ref "SJ7") (pin "1") (pinfunction "1_1") (pintype "passive"))
      (node (ref "SX31") (pin "1") (pinfunction "P$1_1") (pintype "bidirectional"))
    )
    (net (code "81") (name "TX0") (class "Default")
      (node (ref "K1") (pin "40") (pinfunction "PTB17_40") (pintype "bidirectional"))
      (node (ref "SJ8") (pin "1") (pinfunction "1_1") (pintype "passive"))
      (node (ref "SX30") (pin "1") (pinfunction "P$1_1") (pintype "bidirectional"))
    )
    (net (code "82") (name "VUSB") (class "Default")
      (node (ref "C15") (pin "1") (pinfunction "1_1") (pintype "passive"))
      (node (ref "C17") (pin "1") (pinfunction "1_1") (pintype "passive"))
      (node (ref "R10") (pin "2") (pinfunction "2_2") (pintype "passive"))
      (node (ref "R11") (pin "2") (pinfunction "2_2") (pintype "passive"))
      (node (ref "R12") (pin "2") (pinfunction "2_2") (pintype "passive"))
      (node (ref "R9") (pin "2") (pinfunction "2_2") (pintype "passive"))
      (node (ref "SJ2") (pin "1") (pinfunction "1_1") (pintype "passive"))
      (node (ref "T2") (pin "1") (pinfunction "IN_1") (pintype "bidirectional"))
      (node (ref "U1") (pin "13") (pinfunction "VDD_13") (pintype "bidirectional"))
      (node (ref "U2") (pin "13") (pinfunction "VDDIO_13") (pintype "bidirectional"))
      (node (ref "U2") (pin "2") (pinfunction "VDD_2") (pintype "bidirectional"))
      (node (ref "U2") (pin "4") (pinfunction "S1_4") (pintype "bidirectional"))
      (node (ref "X2") (pin "1") (pinfunction "1_1") (pintype "passive"))
    )
    (net (code "83") (name "unconnected-(K1-VREGIN-Pad8)") (class "Default")
      (node (ref "K1") (pin "8") (pinfunction "VREGIN_8") (pintype "bidirectional"))
    )
    (net (code "84") (name "unconnected-(K2-PTA0-Pad30)") (class "Default")
      (node (ref "K2") (pin "30") (pinfunction "PTA0_30") (pintype "bidirectional"))
    )
    (net (code "85") (name "unconnected-(K2-PTA1-Pad31)") (class "Default")
      (node (ref "K2") (pin "31") (pinfunction "PTA1_31") (pintype "bidirectional"))
    )
    (net (code "86") (name "unconnected-(K2-PTA2-Pad32)") (class "Default")
      (node (ref "K2") (pin "32") (pinfunction "PTA2_32") (pintype "bidirectional"))
    )
    (net (code "87") (name "unconnected-(K2-PTA5-Pad9)") (class "Default")
      (node (ref "K2") (pin "9") (pinfunction "PTA5_9") (pintype "bidirectional"))
    )
    (net (code "88") (name "unconnected-(K2-PTB3-Pad23)") (class "Default")
      (node (ref "K2") (pin "23") (pinfunction "PTB3_23") (pintype "bidirectional"))
    )
    (net (code "89") (name "unconnected-(K2-PTB4-Pad24)") (class "Default")
      (node (ref "K2") (pin "24") (pinfunction "PTB4_24") (pintype "bidirectional"))
    )
    (net (code "90") (name "unconnected-(U2-DRDY-Pad15)") (class "Default")
      (node (ref "U2") (pin "15") (pinfunction "DRDY_15") (pintype "bidirectional"))
    )
    (net (code "91") (name "unconnected-(U2-NC-Pad3)") (class "Default")
      (node (ref "U2") (pin "3") (pinfunction "NC_3") (pintype "bidirectional"))
    )
    (net (code "92") (name "unconnected-(U2-NC-Pad5)") (class "Default")
      (node (ref "U2") (pin "5") (pinfunction "NC_5") (pintype "bidirectional"))
    )
    (net (code "93") (name "unconnected-(U2-NC-Pad6)") (class "Default")
      (node (ref "U2") (pin "6") (pinfunction "NC_6") (pintype "bidirectional"))
    )
    (net (code "94") (name "unconnected-(U2-NC-Pad7)") (class "Default")
      (node (ref "U2") (pin "7") (pinfunction "NC_7") (pintype "bidirectional"))
    )
    (net (code "95") (name "unconnected-(U2-NC-Pad14)") (class "Default")
      (node (ref "U2") (pin "14") (pinfunction "NC_14") (pintype "bidirectional"))
    )
    (net (code "96") (name "unconnected-(U3-AIO0-Pad9)") (class "Default")
      (node (ref "U3") (pin "9") (pinfunction "AIO0_9") (pintype "bidirectional"))
    )
    (net (code "97") (name "unconnected-(U3-AIO1-Pad10)") (class "Default")
      (node (ref "U3") (pin "10") (pinfunction "AIO1_10") (pintype "bidirectional"))
    )
    (net (code "98") (name "unconnected-(U3-CLK-Pad19)") (class "Default")
      (node (ref "U3") (pin "19") (pinfunction "CLK_19") (pintype "bidirectional"))
    )
    (net (code "99") (name "unconnected-(U3-CSB-Pad16)") (class "Default")
      (node (ref "U3") (pin "16") (pinfunction "CSB_16") (pintype "bidirectional"))
    )
    (net (code "100") (name "unconnected-(U3-CTS-Pad3)") (class "Default")
      (node (ref "U3") (pin "3") (pinfunction "CTS_3") (pintype "bidirectional"))
    )
    (net (code "101") (name "unconnected-(U3-GND1-Pad21)") (class "Default")
      (node (ref "U3") (pin "21") (pinfunction "GND1_21") (pintype "bidirectional"))
    )
    (net (code "102") (name "unconnected-(U3-GND2-Pad22)") (class "Default")
      (node (ref "U3") (pin "22") (pinfunction "GND2_22") (pintype "bidirectional"))
    )
    (net (code "103") (name "unconnected-(U3-MISO-Pad18)") (class "Default")
      (node (ref "U3") (pin "18") (pinfunction "MISO_18") (pintype "bidirectional"))
    )
    (net (code "104") (name "unconnected-(U3-MOSI-Pad17)") (class "Default")
      (node (ref "U3") (pin "17") (pinfunction "MOSI_17") (pintype "bidirectional"))
    )
    (net (code "105") (name "unconnected-(U3-NC-Pad14)") (class "Default")
      (node (ref "U3") (pin "14") (pinfunction "NC_14") (pintype "bidirectional"))
    )
    (net (code "106") (name "unconnected-(U3-PCM_CLK-Pad5)") (class "Default")
      (node (ref "U3") (pin "5") (pinfunction "PCM_CLK_5") (pintype "bidirectional"))
    )
    (net (code "107") (name "unconnected-(U3-PCM_IN-Pad7)") (class "Default")
      (node (ref "U3") (pin "7") (pinfunction "PCM_IN_7") (pintype "bidirectional"))
    )
    (net (code "108") (name "unconnected-(U3-PCM_OUT-Pad6)") (class "Default")
      (node (ref "U3") (pin "6") (pinfunction "PCM_OUT_6") (pintype "bidirectional"))
    )
    (net (code "109") (name "unconnected-(U3-PCN_SYNC-Pad8)") (class "Default")
      (node (ref "U3") (pin "8") (pinfunction "PCN_SYNC_8") (pintype "bidirectional"))
    )
    (net (code "110") (name "unconnected-(U3-PIO0-Pad23)") (class "Default")
      (node (ref "U3") (pin "23") (pinfunction "PIO0_23") (pintype "bidirectional"))
    )
    (net (code "111") (name "unconnected-(U3-PIO1-Pad24)") (class "Default")
      (node (ref "U3") (pin "24") (pinfunction "PIO1_24") (pintype "bidirectional"))
    )
    (net (code "112") (name "unconnected-(U3-PIO2-Pad25)") (class "Default")
      (node (ref "U3") (pin "25") (pinfunction "PIO2_25") (pintype "bidirectional"))
    )
    (net (code "113") (name "unconnected-(U3-PIO3-Pad26)") (class "Default")
      (node (ref "U3") (pin "26") (pinfunction "PIO3_26") (pintype "bidirectional"))
    )
    (net (code "114") (name "unconnected-(U3-PIO4-Pad27)") (class "Default")
      (node (ref "U3") (pin "27") (pinfunction "PIO4_27") (pintype "bidirectional"))
    )
    (net (code "115") (name "unconnected-(U3-PIO5-Pad28)") (class "Default")
      (node (ref "U3") (pin "28") (pinfunction "PIO5_28") (pintype "bidirectional"))
    )
    (net (code "116") (name "unconnected-(U3-PIO6-Pad29)") (class "Default")
      (node (ref "U3") (pin "29") (pinfunction "PIO6_29") (pintype "bidirectional"))
    )
    (net (code "117") (name "unconnected-(U3-PIO7-Pad30)") (class "Default")
      (node (ref "U3") (pin "30") (pinfunction "PIO7_30") (pintype "bidirectional"))
    )
    (net (code "118") (name "unconnected-(U3-PIO8-Pad31)") (class "Default")
      (node (ref "U3") (pin "31") (pinfunction "PIO8_31") (pintype "bidirectional"))
    )
    (net (code "119") (name "unconnected-(U3-PIO9-Pad32)") (class "Default")
      (node (ref "U3") (pin "32") (pinfunction "PIO9_32") (pintype "bidirectional"))
    )
    (net (code "120") (name "unconnected-(U3-PIO10-Pad33)") (class "Default")
      (node (ref "U3") (pin "33") (pinfunction "PIO10_33") (pintype "bidirectional"))
    )
    (net (code "121") (name "unconnected-(U3-PIO11-Pad34)") (class "Default")
      (node (ref "U3") (pin "34") (pinfunction "PIO11_34") (pintype "bidirectional"))
    )
    (net (code "122") (name "unconnected-(U3-RST-Pad11)") (class "Default")
      (node (ref "U3") (pin "11") (pinfunction "RST_11") (pintype "bidirectional"))
    )
    (net (code "123") (name "unconnected-(U3-RTS-Pad4)") (class "Default")
      (node (ref "U3") (pin "4") (pinfunction "RTS_4") (pintype "bidirectional"))
    )
    (net (code "124") (name "unconnected-(U3-VBUSD+-Pad20)") (class "Default")
      (node (ref "U3") (pin "20") (pinfunction "VBUSD+_20") (pintype "bidirectional"))
    )
    (net (code "125") (name "unconnected-(U3-VBUSD--Pad15)") (class "Default")
      (node (ref "U3") (pin "15") (pinfunction "VBUSD-_15") (pintype "bidirectional"))
    )
  )
)
